# B136B.net
KiCad netlist of a schematic drawn in EAGLE
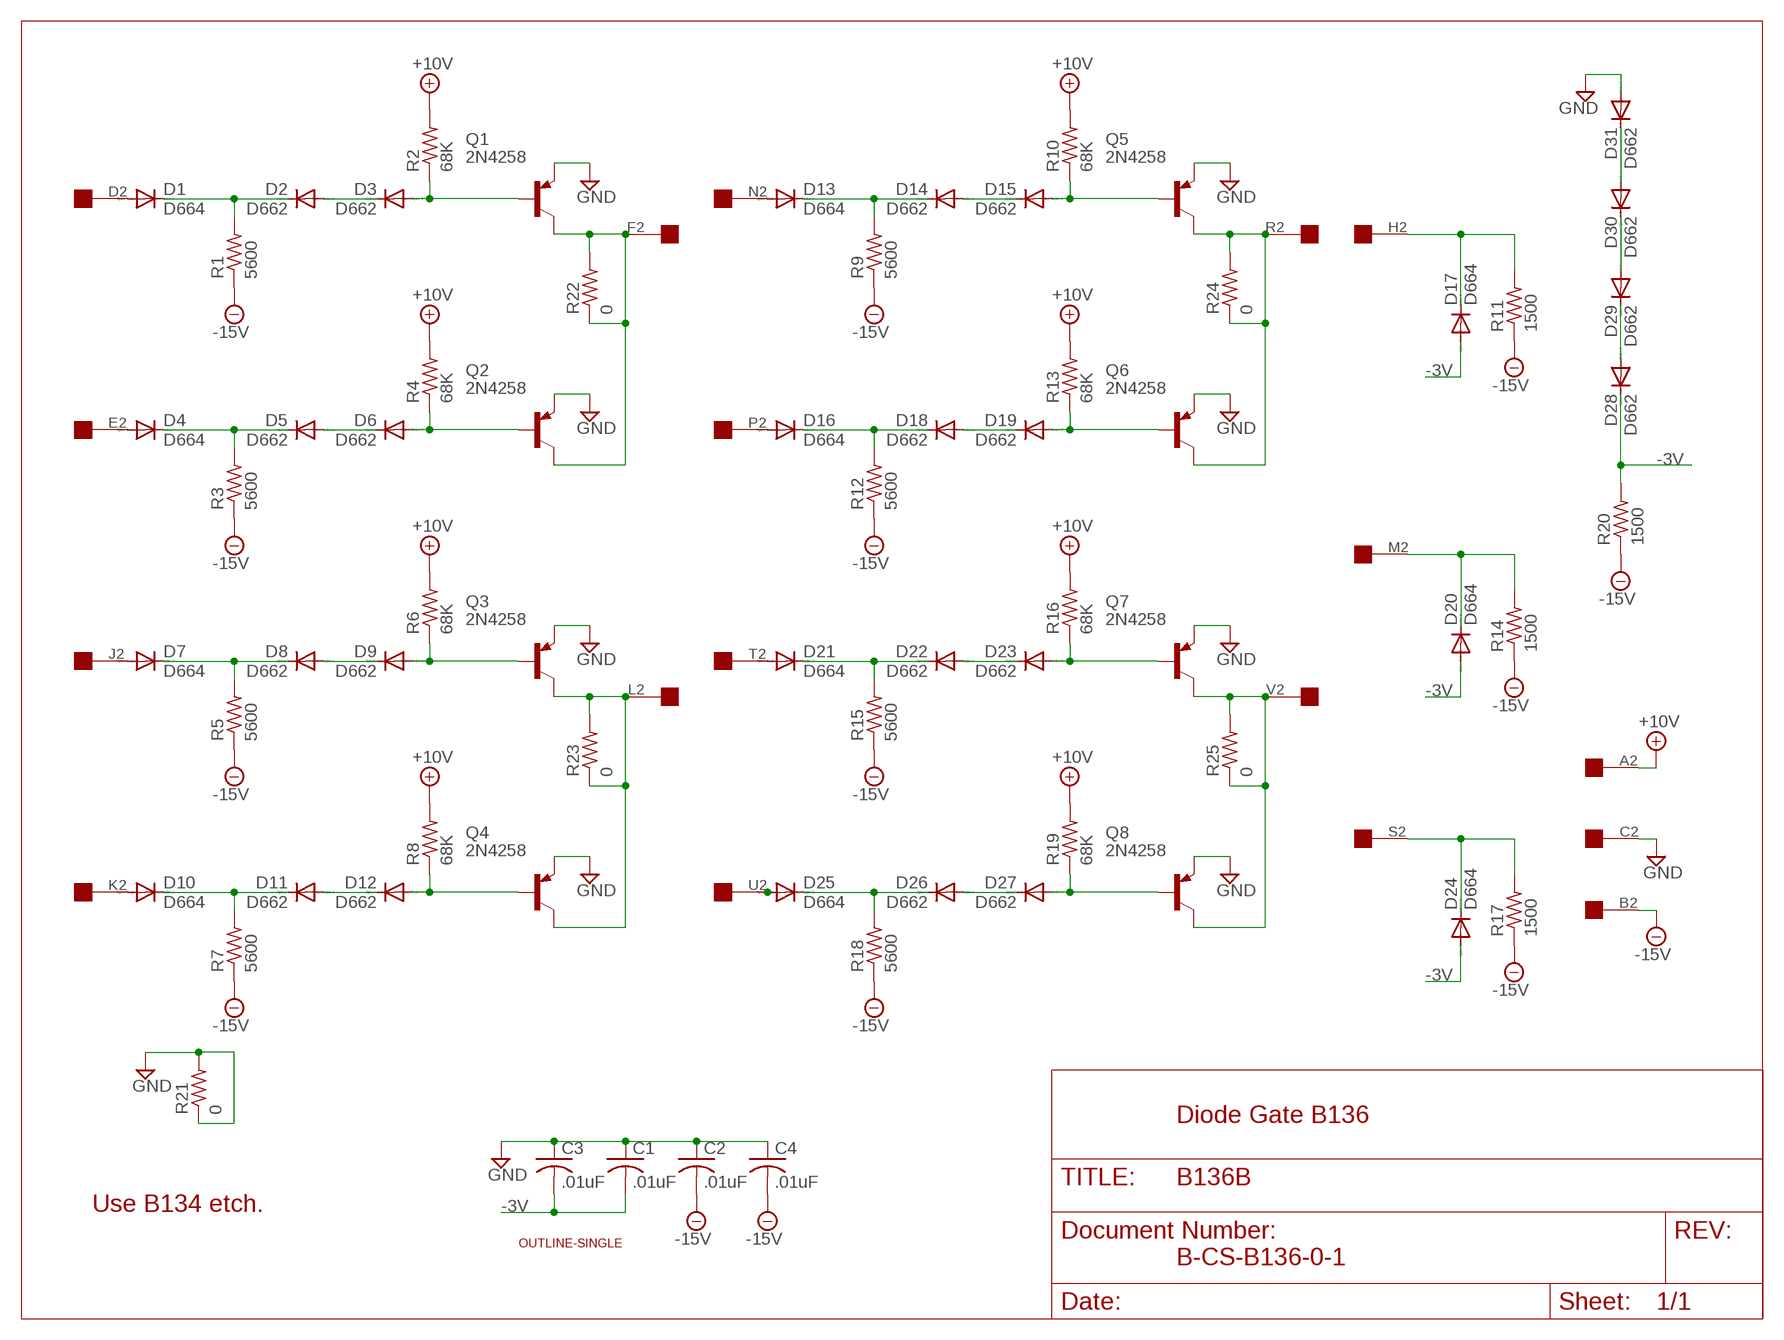
[diagram p0: schematic, sheet 1]

(export (version "E")
  (design (tool "Eeschema 10.0.6"))
  (components
    (comp (ref "C1")
      (value ".01uF")
      (footprint "eagle-import:C063-025X075")
      (libsource (lib "eagle-import") (part "C-US"))
    )
    (comp (ref "C2")
      (value ".01uF")
      (footprint "eagle-import:C063-025X075")
      (libsource (lib "eagle-import") (part "C-US"))
    )
    (comp (ref "C3")
      (value ".01uF")
      (footprint "eagle-import:C063-025X075")
      (libsource (lib "eagle-import") (part "C-US"))
    )
    (comp (ref "C4")
      (value ".01uF")
      (footprint "eagle-import:C063-025X075")
      (libsource (lib "eagle-import") (part "C-US"))
    )
    (comp (ref "D1")
      (value "D664")
      (footprint "eagle-import:DO35-10")
      (libsource (lib "eagle-import") (part "DIODE-DO35-10"))
    )
    (comp (ref "D2")
      (value "D662")
      (footprint "eagle-import:DO35-10")
      (libsource (lib "eagle-import") (part "DIODE-DO35-10"))
    )
    (comp (ref "D3")
      (value "D662")
      (footprint "eagle-import:DO35-10")
      (libsource (lib "eagle-import") (part "DIODE-DO35-10"))
    )
    (comp (ref "D4")
      (value "D664")
      (footprint "eagle-import:DO35-10")
      (libsource (lib "eagle-import") (part "DIODE-DO35-10"))
    )
    (comp (ref "D5")
      (value "D662")
      (footprint "eagle-import:DO35-10")
      (libsource (lib "eagle-import") (part "DIODE-DO35-10"))
    )
    (comp (ref "D6")
      (value "D662")
      (footprint "eagle-import:DO35-10")
      (libsource (lib "eagle-import") (part "DIODE-DO35-10"))
    )
    (comp (ref "D7")
      (value "D664")
      (footprint "eagle-import:DO35-10")
      (libsource (lib "eagle-import") (part "DIODE-DO35-10"))
    )
    (comp (ref "D8")
      (value "D662")
      (footprint "eagle-import:DO35-10")
      (libsource (lib "eagle-import") (part "DIODE-DO35-10"))
    )
    (comp (ref "D9")
      (value "D662")
      (footprint "eagle-import:DO35-10")
      (libsource (lib "eagle-import") (part "DIODE-DO35-10"))
    )
    (comp (ref "D10")
      (value "D664")
      (footprint "eagle-import:DO35-10")
      (libsource (lib "eagle-import") (part "DIODE-DO35-10"))
    )
    (comp (ref "D11")
      (value "D662")
      (footprint "eagle-import:DO35-10")
      (libsource (lib "eagle-import") (part "DIODE-DO35-10"))
    )
    (comp (ref "D12")
      (value "D662")
      (footprint "eagle-import:DO35-10")
      (libsource (lib "eagle-import") (part "DIODE-DO35-10"))
    )
    (comp (ref "D13")
      (value "D664")
      (footprint "eagle-import:DO35-10")
      (libsource (lib "eagle-import") (part "DIODE-DO35-10"))
    )
    (comp (ref "D14")
      (value "D662")
      (footprint "eagle-import:DO35-10")
      (libsource (lib "eagle-import") (part "DIODE-DO35-10"))
    )
    (comp (ref "D15")
      (value "D662")
      (footprint "eagle-import:DO35-10")
      (libsource (lib "eagle-import") (part "DIODE-DO35-10"))
    )
    (comp (ref "D16")
      (value "D664")
      (footprint "eagle-import:DO35-10")
      (libsource (lib "eagle-import") (part "DIODE-DO35-10"))
    )
    (comp (ref "D17")
      (value "D664")
      (footprint "eagle-import:DO35-10")
      (libsource (lib "eagle-import") (part "DIODE-DO35-10"))
    )
    (comp (ref "D18")
      (value "D662")
      (footprint "eagle-import:DO35-10")
      (libsource (lib "eagle-import") (part "DIODE-DO35-10"))
    )
    (comp (ref "D19")
      (value "D662")
      (footprint "eagle-import:DO35-10")
      (libsource (lib "eagle-import") (part "DIODE-DO35-10"))
    )
    (comp (ref "D20")
      (value "D664")
      (footprint "eagle-import:DO35-10")
      (libsource (lib "eagle-import") (part "DIODE-DO35-10"))
    )
    (comp (ref "D21")
      (value "D664")
      (footprint "eagle-import:DO35-10")
      (libsource (lib "eagle-import") (part "DIODE-DO35-10"))
    )
    (comp (ref "D22")
      (value "D662")
      (footprint "eagle-import:DO35-10")
      (libsource (lib "eagle-import") (part "DIODE-DO35-10"))
    )
    (comp (ref "D23")
      (value "D662")
      (footprint "eagle-import:DO35-10")
      (libsource (lib "eagle-import") (part "DIODE-DO35-10"))
    )
    (comp (ref "D24")
      (value "D664")
      (footprint "eagle-import:DO35-10")
      (libsource (lib "eagle-import") (part "DIODE-DO35-10"))
    )
    (comp (ref "D25")
      (value "D664")
      (footprint "eagle-import:DO35-10")
      (libsource (lib "eagle-import") (part "DIODE-DO35-10"))
    )
    (comp (ref "D26")
      (value "D662")
      (footprint "eagle-import:DO35-10")
      (libsource (lib "eagle-import") (part "DIODE-DO35-10"))
    )
    (comp (ref "D27")
      (value "D662")
      (footprint "eagle-import:DO35-10")
      (libsource (lib "eagle-import") (part "DIODE-DO35-10"))
    )
    (comp (ref "D28")
      (value "D662")
      (footprint "eagle-import:DO35-10")
      (libsource (lib "eagle-import") (part "DIODE-DO35-10"))
    )
    (comp (ref "D29")
      (value "D662")
      (footprint "eagle-import:DO35-10")
      (libsource (lib "eagle-import") (part "DIODE-DO35-10"))
    )
    (comp (ref "D30")
      (value "D662")
      (footprint "eagle-import:DO35-10")
      (libsource (lib "eagle-import") (part "DIODE-DO35-10"))
    )
    (comp (ref "D31")
      (value "D662")
      (footprint "eagle-import:DO35-10")
      (libsource (lib "eagle-import") (part "DIODE-DO35-10"))
    )
    (comp (ref "Q1")
      (value "2N4258")
      (footprint "eagle-import:TO5")
      (libsource (lib "eagle-import") (part "-PNP-TO5"))
    )
    (comp (ref "Q2")
      (value "2N4258")
      (footprint "eagle-import:TO5")
      (libsource (lib "eagle-import") (part "-PNP-TO5"))
    )
    (comp (ref "Q3")
      (value "2N4258")
      (footprint "eagle-import:TO5")
      (libsource (lib "eagle-import") (part "-PNP-TO5"))
    )
    (comp (ref "Q4")
      (value "2N4258")
      (footprint "eagle-import:TO5")
      (libsource (lib "eagle-import") (part "-PNP-TO5"))
    )
    (comp (ref "Q5")
      (value "2N4258")
      (footprint "eagle-import:TO5")
      (libsource (lib "eagle-import") (part "-PNP-TO5"))
    )
    (comp (ref "Q6")
      (value "2N4258")
      (footprint "eagle-import:TO5")
      (libsource (lib "eagle-import") (part "-PNP-TO5"))
    )
    (comp (ref "Q7")
      (value "2N4258")
      (footprint "eagle-import:TO5")
      (libsource (lib "eagle-import") (part "-PNP-TO5"))
    )
    (comp (ref "Q8")
      (value "2N4258")
      (footprint "eagle-import:TO5")
      (libsource (lib "eagle-import") (part "-PNP-TO5"))
    )
    (comp (ref "R1")
      (value "5600")
      (footprint "eagle-import:0207_10")
      (libsource (lib "eagle-import") (part "R-US_0207/10"))
    )
    (comp (ref "R2")
      (value "68K")
      (footprint "eagle-import:0207_10")
      (libsource (lib "eagle-import") (part "R-US_0207/10"))
    )
    (comp (ref "R3")
      (value "5600")
      (footprint "eagle-import:0207_10")
      (libsource (lib "eagle-import") (part "R-US_0207/10"))
    )
    (comp (ref "R4")
      (value "68K")
      (footprint "eagle-import:0207_10")
      (libsource (lib "eagle-import") (part "R-US_0207/10"))
    )
    (comp (ref "R5")
      (value "5600")
      (footprint "eagle-import:0207_10")
      (libsource (lib "eagle-import") (part "R-US_0207/10"))
    )
    (comp (ref "R6")
      (value "68K")
      (footprint "eagle-import:0207_10")
      (libsource (lib "eagle-import") (part "R-US_0207/10"))
    )
    (comp (ref "R7")
      (value "5600")
      (footprint "eagle-import:0207_10")
      (libsource (lib "eagle-import") (part "R-US_0207/10"))
    )
    (comp (ref "R8")
      (value "68K")
      (footprint "eagle-import:0207_10")
      (libsource (lib "eagle-import") (part "R-US_0207/10"))
    )
    (comp (ref "R9")
      (value "5600")
      (footprint "eagle-import:0207_10")
      (libsource (lib "eagle-import") (part "R-US_0207/10"))
    )
    (comp (ref "R10")
      (value "68K")
      (footprint "eagle-import:0207_10")
      (libsource (lib "eagle-import") (part "R-US_0207/10"))
    )
    (comp (ref "R11")
      (value "1500")
      (footprint "eagle-import:0207_10")
      (libsource (lib "eagle-import") (part "R-US_0207/10"))
    )
    (comp (ref "R12")
      (value "5600")
      (footprint "eagle-import:0207_10")
      (libsource (lib "eagle-import") (part "R-US_0207/10"))
    )
    (comp (ref "R13")
      (value "68K")
      (footprint "eagle-import:0207_10")
      (libsource (lib "eagle-import") (part "R-US_0207/10"))
    )
    (comp (ref "R14")
      (value "1500")
      (footprint "eagle-import:0207_10")
      (libsource (lib "eagle-import") (part "R-US_0207/10"))
    )
    (comp (ref "R15")
      (value "5600")
      (footprint "eagle-import:0207_10")
      (libsource (lib "eagle-import") (part "R-US_0207/10"))
    )
    (comp (ref "R16")
      (value "68K")
      (footprint "eagle-import:0207_10")
      (libsource (lib "eagle-import") (part "R-US_0207/10"))
    )
    (comp (ref "R17")
      (value "1500")
      (footprint "eagle-import:0207_10")
      (libsource (lib "eagle-import") (part "R-US_0207/10"))
    )
    (comp (ref "R18")
      (value "5600")
      (footprint "eagle-import:0207_10")
      (libsource (lib "eagle-import") (part "R-US_0207/10"))
    )
    (comp (ref "R19")
      (value "68K")
      (footprint "eagle-import:0207_10")
      (libsource (lib "eagle-import") (part "R-US_0207/10"))
    )
    (comp (ref "R20")
      (value "1500")
      (footprint "eagle-import:0207_10")
      (libsource (lib "eagle-import") (part "R-US_0207/10"))
    )
    (comp (ref "R21")
      (value "0")
      (footprint "eagle-import:0207_10")
      (libsource (lib "eagle-import") (part "R-US_0207/10"))
    )
    (comp (ref "R22")
      (value "0")
      (footprint "eagle-import:0207_10")
      (libsource (lib "eagle-import") (part "R-US_0207/10"))
    )
    (comp (ref "R23")
      (value "0")
      (footprint "eagle-import:0207_10")
      (libsource (lib "eagle-import") (part "R-US_0207/10"))
    )
    (comp (ref "R24")
      (value "0")
      (footprint "eagle-import:0207_10")
      (libsource (lib "eagle-import") (part "R-US_0207/10"))
    )
    (comp (ref "R25")
      (value "0")
      (footprint "eagle-import:0207_10")
      (libsource (lib "eagle-import") (part "R-US_0207/10"))
    )
    (comp (ref "U$1")
      (value "OUTLINE-SINGLE")
      (footprint "eagle-import:SINGLE")
      (libsource (lib "eagle-import") (part "OUTLINE-SINGLE"))
    )
    (comp (ref "U$2")
      (value "EDGE-1")
      (footprint "eagle-import:EDGE-CON1")
      (libsource (lib "eagle-import") (part "EDGE-1"))
    )
  )
  (nets
    (net (code "1") (name "+10V") (class "Default")
      (node (ref "R10") (pin "2") (pinfunction "2_2") (pintype "passive"))
      (node (ref "R13") (pin "2") (pinfunction "2_2") (pintype "passive"))
      (node (ref "R16") (pin "2") (pinfunction "2_2") (pintype "passive"))
      (node (ref "R19") (pin "2") (pinfunction "2_2") (pintype "passive"))
      (node (ref "R2") (pin "2") (pinfunction "2_2") (pintype "passive"))
      (node (ref "R4") (pin "2") (pinfunction "2_2") (pintype "passive"))
      (node (ref "R6") (pin "2") (pinfunction "2_2") (pintype "passive"))
      (node (ref "R8") (pin "2") (pinfunction "2_2") (pintype "passive"))
      (node (ref "U$2") (pin "A2") (pinfunction "1_A2") (pintype "bidirectional"))
    )
    (net (code "2") (name "-15V") (class "Default")
      (node (ref "C2") (pin "2") (pinfunction "2_2") (pintype "passive"))
      (node (ref "C4") (pin "2") (pinfunction "2_2") (pintype "passive"))
      (node (ref "R1") (pin "1") (pinfunction "1_1") (pintype "passive"))
      (node (ref "R11") (pin "1") (pinfunction "1_1") (pintype "passive"))
      (node (ref "R12") (pin "1") (pinfunction "1_1") (pintype "passive"))
      (node (ref "R14") (pin "1") (pinfunction "1_1") (pintype "passive"))
      (node (ref "R15") (pin "1") (pinfunction "1_1") (pintype "passive"))
      (node (ref "R17") (pin "1") (pinfunction "1_1") (pintype "passive"))
      (node (ref "R18") (pin "1") (pinfunction "1_1") (pintype "passive"))
      (node (ref "R20") (pin "1") (pinfunction "1_1") (pintype "passive"))
      (node (ref "R3") (pin "1") (pinfunction "1_1") (pintype "passive"))
      (node (ref "R5") (pin "1") (pinfunction "1_1") (pintype "passive"))
      (node (ref "R7") (pin "1") (pinfunction "1_1") (pintype "passive"))
      (node (ref "R9") (pin "1") (pinfunction "1_1") (pintype "passive"))
      (node (ref "U$2") (pin "B2") (pinfunction "1_B2") (pintype "bidirectional"))
    )
    (net (code "3") (name "/-3V") (class "Default")
      (node (ref "C1") (pin "2") (pinfunction "2_2") (pintype "passive"))
      (node (ref "C3") (pin "2") (pinfunction "2_2") (pintype "passive"))
      (node (ref "D17") (pin "A") (pinfunction "A_A") (pintype "passive"))
      (node (ref "D20") (pin "A") (pinfunction "A_A") (pintype "passive"))
      (node (ref "D24") (pin "A") (pinfunction "A_A") (pintype "passive"))
      (node (ref "D28") (pin "C") (pinfunction "C_C") (pintype "passive"))
      (node (ref "R20") (pin "2") (pinfunction "2_2") (pintype "passive"))
    )
    (net (code "4") (name "GND") (class "Default")
      (node (ref "C1") (pin "1") (pinfunction "1_1") (pintype "passive"))
      (node (ref "C2") (pin "1") (pinfunction "1_1") (pintype "passive"))
      (node (ref "C3") (pin "1") (pinfunction "1_1") (pintype "passive"))
      (node (ref "C4") (pin "1") (pinfunction "1_1") (pintype "passive"))
      (node (ref "D31") (pin "A") (pinfunction "A_A") (pintype "passive"))
      (node (ref "Q1") (pin "1") (pinfunction "E_1") (pintype "passive"))
      (node (ref "Q2") (pin "1") (pinfunction "E_1") (pintype "passive"))
      (node (ref "Q3") (pin "1") (pinfunction "E_1") (pintype "passive"))
      (node (ref "Q4") (pin "1") (pinfunction "E_1") (pintype "passive"))
      (node (ref "Q5") (pin "1") (pinfunction "E_1") (pintype "passive"))
      (node (ref "Q6") (pin "1") (pinfunction "E_1") (pintype "passive"))
      (node (ref "Q7") (pin "1") (pinfunction "E_1") (pintype "passive"))
      (node (ref "Q8") (pin "1") (pinfunction "E_1") (pintype "passive"))
      (node (ref "R21") (pin "1") (pinfunction "1_1") (pintype "passive"))
      (node (ref "R21") (pin "2") (pinfunction "2_2") (pintype "passive"))
      (node (ref "U$2") (pin "C2") (pinfunction "1_C2") (pintype "bidirectional"))
    )
    (net (code "5") (name "Net-(D1-PadC)") (class "Default")
      (node (ref "D1") (pin "C") (pinfunction "C_C") (pintype "passive"))
      (node (ref "D2") (pin "C") (pinfunction "C_C") (pintype "passive"))
      (node (ref "R1") (pin "2") (pinfunction "2_2") (pintype "passive"))
    )
    (net (code "6") (name "Net-(D2-PadA)") (class "Default")
      (node (ref "D2") (pin "A") (pinfunction "A_A") (pintype "passive"))
      (node (ref "D3") (pin "C") (pinfunction "C_C") (pintype "passive"))
    )
    (net (code "7") (name "Net-(D4-PadC)") (class "Default")
      (node (ref "D4") (pin "C") (pinfunction "C_C") (pintype "passive"))
      (node (ref "D5") (pin "C") (pinfunction "C_C") (pintype "passive"))
      (node (ref "R3") (pin "2") (pinfunction "2_2") (pintype "passive"))
    )
    (net (code "8") (name "Net-(D5-PadA)") (class "Default")
      (node (ref "D5") (pin "A") (pinfunction "A_A") (pintype "passive"))
      (node (ref "D6") (pin "C") (pinfunction "C_C") (pintype "passive"))
    )
    (net (code "9") (name "Net-(D7-PadC)") (class "Default")
      (node (ref "D7") (pin "C") (pinfunction "C_C") (pintype "passive"))
      (node (ref "D8") (pin "C") (pinfunction "C_C") (pintype "passive"))
      (node (ref "R5") (pin "2") (pinfunction "2_2") (pintype "passive"))
    )
    (net (code "10") (name "Net-(D8-PadA)") (class "Default")
      (node (ref "D8") (pin "A") (pinfunction "A_A") (pintype "passive"))
      (node (ref "D9") (pin "C") (pinfunction "C_C") (pintype "passive"))
    )
    (net (code "11") (name "Net-(D10-PadC)") (class "Default")
      (node (ref "D10") (pin "C") (pinfunction "C_C") (pintype "passive"))
      (node (ref "D11") (pin "C") (pinfunction "C_C") (pintype "passive"))
      (node (ref "R7") (pin "2") (pinfunction "2_2") (pintype "passive"))
    )
    (net (code "12") (name "Net-(D11-PadA)") (class "Default")
      (node (ref "D11") (pin "A") (pinfunction "A_A") (pintype "passive"))
      (node (ref "D12") (pin "C") (pinfunction "C_C") (pintype "passive"))
    )
    (net (code "13") (name "Net-(D13-PadC)") (class "Default")
      (node (ref "D13") (pin "C") (pinfunction "C_C") (pintype "passive"))
      (node (ref "D14") (pin "C") (pinfunction "C_C") (pintype "passive"))
      (node (ref "R9") (pin "2") (pinfunction "2_2") (pintype "passive"))
    )
    (net (code "14") (name "Net-(D14-PadA)") (class "Default")
      (node (ref "D14") (pin "A") (pinfunction "A_A") (pintype "passive"))
      (node (ref "D15") (pin "C") (pinfunction "C_C") (pintype "passive"))
    )
    (net (code "15") (name "Net-(D16-PadC)") (class "Default")
      (node (ref "D16") (pin "C") (pinfunction "C_C") (pintype "passive"))
      (node (ref "D18") (pin "C") (pinfunction "C_C") (pintype "passive"))
      (node (ref "R12") (pin "2") (pinfunction "2_2") (pintype "passive"))
    )
    (net (code "16") (name "Net-(D18-PadA)") (class "Default")
      (node (ref "D18") (pin "A") (pinfunction "A_A") (pintype "passive"))
      (node (ref "D19") (pin "C") (pinfunction "C_C") (pintype "passive"))
    )
    (net (code "17") (name "Net-(D21-PadC)") (class "Default")
      (node (ref "D21") (pin "C") (pinfunction "C_C") (pintype "passive"))
      (node (ref "D22") (pin "C") (pinfunction "C_C") (pintype "passive"))
      (node (ref "R15") (pin "2") (pinfunction "2_2") (pintype "passive"))
    )
    (net (code "18") (name "Net-(D22-PadA)") (class "Default")
      (node (ref "D22") (pin "A") (pinfunction "A_A") (pintype "passive"))
      (node (ref "D23") (pin "C") (pinfunction "C_C") (pintype "passive"))
    )
    (net (code "19") (name "Net-(D25-PadC)") (class "Default")
      (node (ref "D25") (pin "C") (pinfunction "C_C") (pintype "passive"))
      (node (ref "D26") (pin "C") (pinfunction "C_C") (pintype "passive"))
      (node (ref "R18") (pin "2") (pinfunction "2_2") (pintype "passive"))
    )
    (net (code "20") (name "Net-(D26-PadA)") (class "Default")
      (node (ref "D26") (pin "A") (pinfunction "A_A") (pintype "passive"))
      (node (ref "D27") (pin "C") (pinfunction "C_C") (pintype "passive"))
    )
    (net (code "21") (name "Net-(D28-PadA)") (class "Default")
      (node (ref "D28") (pin "A") (pinfunction "A_A") (pintype "passive"))
      (node (ref "D29") (pin "C") (pinfunction "C_C") (pintype "passive"))
    )
    (net (code "22") (name "Net-(D29-PadA)") (class "Default")
      (node (ref "D29") (pin "A") (pinfunction "A_A") (pintype "passive"))
      (node (ref "D30") (pin "C") (pinfunction "C_C") (pintype "passive"))
    )
    (net (code "23") (name "Net-(D30-PadA)") (class "Default")
      (node (ref "D30") (pin "A") (pinfunction "A_A") (pintype "passive"))
      (node (ref "D31") (pin "C") (pinfunction "C_C") (pintype "passive"))
    )
    (net (code "24") (name "Net-(Q1-B)") (class "Default")
      (node (ref "D3") (pin "A") (pinfunction "A_A") (pintype "passive"))
      (node (ref "Q1") (pin "2") (pinfunction "B_2") (pintype "passive"))
      (node (ref "R2") (pin "1") (pinfunction "1_1") (pintype "passive"))
    )
    (net (code "25") (name "Net-(Q1-C)") (class "Default")
      (node (ref "Q1") (pin "3") (pinfunction "C_3") (pintype "passive"))
      (node (ref "Q2") (pin "3") (pinfunction "C_3") (pintype "passive"))
      (node (ref "R22") (pin "1") (pinfunction "1_1") (pintype "passive"))
      (node (ref "R22") (pin "2") (pinfunction "2_2") (pintype "passive"))
      (node (ref "U$2") (pin "F2") (pinfunction "1_F2") (pintype "bidirectional"))
    )
    (net (code "26") (name "Net-(Q2-B)") (class "Default")
      (node (ref "D6") (pin "A") (pinfunction "A_A") (pintype "passive"))
      (node (ref "Q2") (pin "2") (pinfunction "B_2") (pintype "passive"))
      (node (ref "R4") (pin "1") (pinfunction "1_1") (pintype "passive"))
    )
    (net (code "27") (name "Net-(Q3-B)") (class "Default")
      (node (ref "D9") (pin "A") (pinfunction "A_A") (pintype "passive"))
      (node (ref "Q3") (pin "2") (pinfunction "B_2") (pintype "passive"))
      (node (ref "R6") (pin "1") (pinfunction "1_1") (pintype "passive"))
    )
    (net (code "28") (name "Net-(Q3-C)") (class "Default")
      (node (ref "Q3") (pin "3") (pinfunction "C_3") (pintype "passive"))
      (node (ref "Q4") (pin "3") (pinfunction "C_3") (pintype "passive"))
      (node (ref "R23") (pin "1") (pinfunction "1_1") (pintype "passive"))
      (node (ref "R23") (pin "2") (pinfunction "2_2") (pintype "passive"))
      (node (ref "U$2") (pin "L2") (pinfunction "1_L2") (pintype "bidirectional"))
    )
    (net (code "29") (name "Net-(Q4-B)") (class "Default")
      (node (ref "D12") (pin "A") (pinfunction "A_A") (pintype "passive"))
      (node (ref "Q4") (pin "2") (pinfunction "B_2") (pintype "passive"))
      (node (ref "R8") (pin "1") (pinfunction "1_1") (pintype "passive"))
    )
    (net (code "30") (name "Net-(Q5-B)") (class "Default")
      (node (ref "D15") (pin "A") (pinfunction "A_A") (pintype "passive"))
      (node (ref "Q5") (pin "2") (pinfunction "B_2") (pintype "passive"))
      (node (ref "R10") (pin "1") (pinfunction "1_1") (pintype "passive"))
    )
    (net (code "31") (name "Net-(Q5-C)") (class "Default")
      (node (ref "Q5") (pin "3") (pinfunction "C_3") (pintype "passive"))
      (node (ref "Q6") (pin "3") (pinfunction "C_3") (pintype "passive"))
      (node (ref "R24") (pin "1") (pinfunction "1_1") (pintype "passive"))
      (node (ref "R24") (pin "2") (pinfunction "2_2") (pintype "passive"))
      (node (ref "U$2") (pin "R2") (pinfunction "1_R2") (pintype "bidirectional"))
    )
    (net (code "32") (name "Net-(Q6-B)") (class "Default")
      (node (ref "D19") (pin "A") (pinfunction "A_A") (pintype "passive"))
      (node (ref "Q6") (pin "2") (pinfunction "B_2") (pintype "passive"))
      (node (ref "R13") (pin "1") (pinfunction "1_1") (pintype "passive"))
    )
    (net (code "33") (name "Net-(Q7-B)") (class "Default")
      (node (ref "D23") (pin "A") (pinfunction "A_A") (pintype "passive"))
      (node (ref "Q7") (pin "2") (pinfunction "B_2") (pintype "passive"))
      (node (ref "R16") (pin "1") (pinfunction "1_1") (pintype "passive"))
    )
    (net (code "34") (name "Net-(Q7-C)") (class "Default")
      (node (ref "Q7") (pin "3") (pinfunction "C_3") (pintype "passive"))
      (node (ref "Q8") (pin "3") (pinfunction "C_3") (pintype "passive"))
      (node (ref "R25") (pin "1") (pinfunction "1_1") (pintype "passive"))
      (node (ref "R25") (pin "2") (pinfunction "2_2") (pintype "passive"))
      (node (ref "U$2") (pin "V2") (pinfunction "1_V2") (pintype "bidirectional"))
    )
    (net (code "35") (name "Net-(Q8-B)") (class "Default")
      (node (ref "D27") (pin "A") (pinfunction "A_A") (pintype "passive"))
      (node (ref "Q8") (pin "2") (pinfunction "B_2") (pintype "passive"))
      (node (ref "R19") (pin "1") (pinfunction "1_1") (pintype "passive"))
    )
    (net (code "36") (name "Net-(U$2D-1)") (class "Default")
      (node (ref "D1") (pin "A") (pinfunction "A_A") (pintype "passive"))
      (node (ref "U$2") (pin "D2") (pinfunction "1_D2") (pintype "bidirectional"))
    )
    (net (code "37") (name "Net-(U$2E-1)") (class "Default")
      (node (ref "D4") (pin "A") (pinfunction "A_A") (pintype "passive"))
      (node (ref "U$2") (pin "E2") (pinfunction "1_E2") (pintype "bidirectional"))
    )
    (net (code "38") (name "Net-(U$2G-1)") (class "Default")
      (node (ref "D17") (pin "C") (pinfunction "C_C") (pintype "passive"))
      (node (ref "R11") (pin "2") (pinfunction "2_2") (pintype "passive"))
      (node (ref "U$2") (pin "H2") (pinfunction "1_H2") (pintype "bidirectional"))
    )
    (net (code "39") (name "Net-(U$2H-1)") (class "Default")
      (node (ref "D7") (pin "A") (pinfunction "A_A") (pintype "passive"))
      (node (ref "U$2") (pin "J2") (pinfunction "1_J2") (pintype "bidirectional"))
    )
    (net (code "40") (name "Net-(U$2I-1)") (class "Default")
      (node (ref "D10") (pin "A") (pinfunction "A_A") (pintype "passive"))
      (node (ref "U$2") (pin "K2") (pinfunction "1_K2") (pintype "bidirectional"))
    )
    (net (code "41") (name "Net-(U$2K-1)") (class "Default")
      (node (ref "D20") (pin "C") (pinfunction "C_C") (pintype "passive"))
      (node (ref "R14") (pin "2") (pinfunction "2_2") (pintype "passive"))
      (node (ref "U$2") (pin "M2") (pinfunction "1_M2") (pintype "bidirectional"))
    )
    (net (code "42") (name "Net-(U$2L-1)") (class "Default")
      (node (ref "D13") (pin "A") (pinfunction "A_A") (pintype "passive"))
      (node (ref "U$2") (pin "N2") (pinfunction "1_N2") (pintype "bidirectional"))
    )
    (net (code "43") (name "Net-(U$2M-1)") (class "Default")
      (node (ref "D16") (pin "A") (pinfunction "A_A") (pintype "passive"))
      (node (ref "U$2") (pin "P2") (pinfunction "1_P2") (pintype "bidirectional"))
    )
    (net (code "44") (name "Net-(U$2O-1)") (class "Default")
      (node (ref "D24") (pin "C") (pinfunction "C_C") (pintype "passive"))
      (node (ref "R17") (pin "2") (pinfunction "2_2") (pintype "passive"))
      (node (ref "U$2") (pin "S2") (pinfunction "1_S2") (pintype "bidirectional"))
    )
    (net (code "45") (name "Net-(U$2P-1)") (class "Default")
      (node (ref "D21") (pin "A") (pinfunction "A_A") (pintype "passive"))
      (node (ref "U$2") (pin "T2") (pinfunction "1_T2") (pintype "bidirectional"))
    )
    (net (code "46") (name "Net-(U$2Q-1)") (class "Default")
      (node (ref "D25") (pin "A") (pinfunction "A_A") (pintype "passive"))
      (node (ref "U$2") (pin "U2") (pinfunction "1_U2") (pintype "bidirectional"))
    )
  )
)
